# mega_nhakinh.net
KiCad netlist of a schematic drawn in Altium Designer
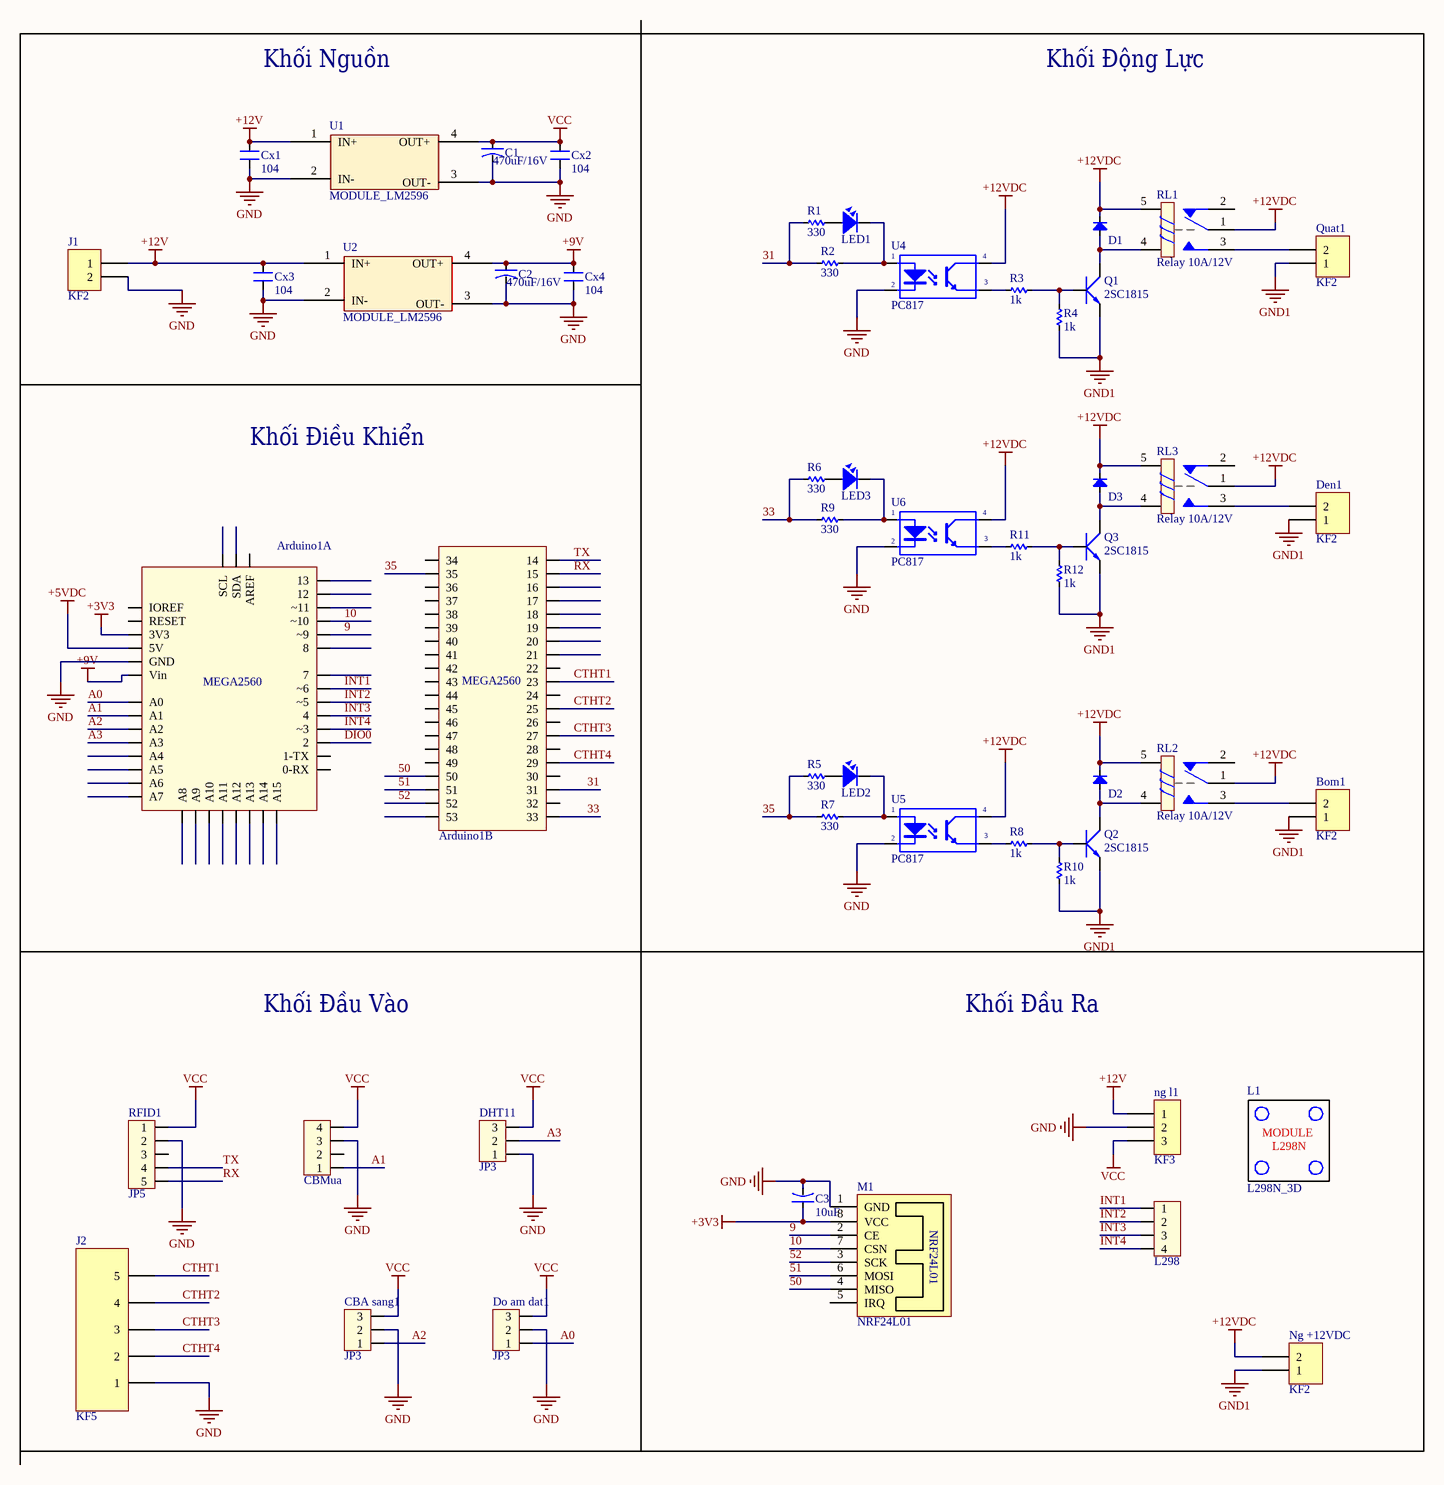
[diagram p0: mega nhakinh.SchDoc]

(export (version "E")
  (design (tool "Eeschema 10.0.6"))
  (components
    (comp (ref "Arduino1")
      (value "Arduino Mega2560")
      (footprint "Arduino MEGA2560")
      (description "Arduino MEGA2560")
      (libsource (lib "LIBRARY") (part "Arduino Mega2560"))
    )
    (comp (ref "Bom1")
      (value "KF2")
      (footprint "KF2-5.08")
      (fields
        (field (name "MANUFACTURER") "Würth Elektronik eiSos GmbH")
        (field (name "PARTNO") "691103110002")
        (field (name "CREATED BY") "Karrer Zheng")
      )
      (libsource (lib "LIBRARY") (part "KF2"))
    )
    (comp (ref "C1")
      (value "470uF/16V")
      (footprint "CA-ALU-10R")
      (description "Capacitor (Semiconductor SIM Model)")
      (fields (field (name "PUBLISHER") "Altium Limited"))
      (libsource (lib "LIBRARY") (part "CN-ALU-DIP"))
    )
    (comp (ref "C2")
      (value "470uF/16V")
      (footprint "CA-ALU-10R")
      (description "Capacitor (Semiconductor SIM Model)")
      (fields (field (name "PUBLISHER") "Altium Limited"))
      (libsource (lib "LIBRARY") (part "CN-ALU-DIP"))
    )
    (comp (ref "C3")
      (value "10uF")
      (footprint "CA-ALU-6.3R")
      (description "Capacitor (Semiconductor SIM Model)")
      (fields (field (name "PUBLISHER") "Altium Limited"))
      (libsource (lib "LIBRARY") (part "CN-ALU-DIP"))
    )
    (comp (ref "CBA sang1")
      (value "JP3")
      (footprint "CON3")
      (description "Connector 3")
      (libsource (lib "lib 1") (part "Con3"))
    )
    (comp (ref "Cx1") (value "104") (footprint "CN2-T") (libsource (lib "LIBRARY") (part "CN")))
    (comp (ref "Cx2") (value "104") (footprint "CN2-T") (libsource (lib "LIBRARY") (part "CN")))
    (comp (ref "Cx3") (value "104") (footprint "CN2-T") (libsource (lib "LIBRARY") (part "CN")))
    (comp (ref "Cx4") (value "104") (footprint "CN2-T") (libsource (lib "LIBRARY") (part "CN")))
    (comp (ref "D1")
      (value "Diode")
      (footprint "DIO-1A-SMALL")
      (description "Default Diode")
      (fields (field (name "PUBLISHER") "Altium Limited"))
      (libsource (lib "LIBRARY") (part "Diode"))
    )
    (comp (ref "D2")
      (value "Diode")
      (footprint "DIO-1A-SMALL")
      (description "Default Diode")
      (fields (field (name "PUBLISHER") "Altium Limited"))
      (libsource (lib "LIBRARY") (part "Diode"))
    )
    (comp (ref "D3")
      (value "Diode")
      (footprint "DIO-1A-SMALL")
      (description "Default Diode")
      (fields (field (name "PUBLISHER") "Altium Limited"))
      (libsource (lib "LIBRARY") (part "Diode"))
    )
    (comp (ref "Den1")
      (value "KF2")
      (footprint "KF2-5.08")
      (fields
        (field (name "MANUFACTURER") "Würth Elektronik eiSos GmbH")
        (field (name "PARTNO") "691103110002")
        (field (name "CREATED BY") "Karrer Zheng")
      )
      (libsource (lib "LIBRARY") (part "KF2"))
    )
    (comp (ref "DHT11")
      (value "JP3")
      (footprint "CON3")
      (description "Connector 3")
      (libsource (lib "lib 1") (part "Con3"))
    )
    (comp (ref "Do am dat1")
      (value "JP3")
      (footprint "CON3")
      (description "Connector 3")
      (libsource (lib "lib 1") (part "Con3"))
    )
    (comp (ref "J1")
      (value "KF2")
      (footprint "KF2-5.08")
      (fields
        (field (name "MANUFACTURER") "Würth Elektronik eiSos GmbH")
        (field (name "PARTNO") "691103110002")
        (field (name "CREATED BY") "Karrer Zheng")
      )
      (libsource (lib "") (part "KF2_1"))
    )
    (comp (ref "J2")
      (value "KF5")
      (footprint "KF5-5")
      (fields
        (field (name "MANUFACTURER") "Würth Elektronik eiSos GmbH")
        (field (name "PARTNO") "691133710005")
        (field (name "CREATED BY") "Baojun Chen")
      )
      (libsource (lib "LIBRARY") (part "KF5"))
    )
    (comp (ref "JP1")
      (value "L298")
      (footprint "CON4")
      (description "Connector 4")
      (libsource (lib "lib 1") (part "Con4"))
    )
    (comp (ref "JP2")
      (value "CBMua")
      (footprint "CON4")
      (description "Connector 4")
      (libsource (lib "") (part "Con4_1"))
    )
    (comp (ref "L1")
      (value "L298N_3D")
      (footprint "BaDinh_Library:L298N_3D")
      (libsource (lib "BaDinh_Library") (part "L298N_3D"))
    )
    (comp (ref "LED1")
      (value "LED")
      (footprint "LED-5MM-BLUE")
      (description "LED Single colour Green and Red")
      (libsource (lib "LIBRARY") (part "LED"))
    )
    (comp (ref "LED2")
      (value "LED")
      (footprint "LED-5MM-BLUE")
      (description "LED Single colour Green and Red")
      (libsource (lib "LIBRARY") (part "LED"))
    )
    (comp (ref "LED3")
      (value "LED")
      (footprint "LED-5MM-BLUE")
      (description "LED Single colour Green and Red")
      (libsource (lib "LIBRARY") (part "LED"))
    )
    (comp (ref "M1") (value "NRF24L01") (footprint "NRF24L01") (libsource (lib "LIBRARY") (part "NRF24L01")))
    (comp (ref "Ng +12VDC")
      (value "KF2")
      (footprint "KF2-5.08")
      (fields
        (field (name "MANUFACTURER") "Würth Elektronik eiSos GmbH")
        (field (name "PARTNO") "691103110002")
        (field (name "CREATED BY") "Karrer Zheng")
      )
      (libsource (lib "LIBRARY") (part "KF2"))
    )
    (comp (ref "ng l1")
      (value "KF3")
      (footprint "KF3-3.5")
      (fields
        (field (name "MANUFACTURER") "Würth Elektronik eiSos GmbH")
        (field (name "PARTNO") "691103110003")
        (field (name "CREATED BY") "Karrer Zheng")
      )
      (libsource (lib "LIBRARY") (part "KF3"))
    )
    (comp (ref "Q1")
      (value "2SC1815")
      (footprint "TO92-123")
      (description "NPN 600mW, ECB")
      (libsource (lib "LIBRARY") (part "2SC1815"))
    )
    (comp (ref "Q2")
      (value "2SC1815")
      (footprint "TO92-123")
      (description "NPN 600mW, ECB")
      (libsource (lib "LIBRARY") (part "2SC1815"))
    )
    (comp (ref "Q3")
      (value "2SC1815")
      (footprint "TO92-123")
      (description "NPN 600mW, ECB")
      (libsource (lib "LIBRARY") (part "2SC1815"))
    )
    (comp (ref "Quat1")
      (value "KF2")
      (footprint "KF2-5.08")
      (fields
        (field (name "MANUFACTURER") "Würth Elektronik eiSos GmbH")
        (field (name "PARTNO") "691103110002")
        (field (name "CREATED BY") "Karrer Zheng")
      )
      (libsource (lib "LIBRARY") (part "KF2"))
    )
    (comp (ref "R1")
      (value "330")
      (footprint "RES-1/4W-SMALL")
      (description "Res")
      (fields
        (field (name "MANUFACTURER") "Generic Components")
        (field (name "PUBLISHER") "Altium Hobart Technology Centre")
      )
      (libsource (lib "LIBRARY") (part "Res"))
    )
    (comp (ref "R2")
      (value "330")
      (footprint "RES-1/4W-SMALL")
      (description "Res")
      (fields
        (field (name "MANUFACTURER") "Generic Components")
        (field (name "PUBLISHER") "Altium Hobart Technology Centre")
      )
      (libsource (lib "LIBRARY") (part "Res"))
    )
    (comp (ref "R3")
      (value "1k")
      (footprint "RES-1/4W-SMALL")
      (description "Res")
      (fields
        (field (name "MANUFACTURER") "Generic Components")
        (field (name "PUBLISHER") "Altium Hobart Technology Centre")
      )
      (libsource (lib "LIBRARY") (part "Res"))
    )
    (comp (ref "R4")
      (value "1k")
      (footprint "RES-1/4W-SMALL")
      (description "Res")
      (fields
        (field (name "MANUFACTURER") "Generic Components")
        (field (name "PUBLISHER") "Altium Hobart Technology Centre")
      )
      (libsource (lib "LIBRARY") (part "Res"))
    )
    (comp (ref "R5")
      (value "330")
      (footprint "RES-1/4W-SMALL")
      (description "Res")
      (fields
        (field (name "MANUFACTURER") "Generic Components")
        (field (name "PUBLISHER") "Altium Hobart Technology Centre")
      )
      (libsource (lib "LIBRARY") (part "Res"))
    )
    (comp (ref "R6")
      (value "330")
      (footprint "RES-1/4W-SMALL")
      (description "Res")
      (fields
        (field (name "MANUFACTURER") "Generic Components")
        (field (name "PUBLISHER") "Altium Hobart Technology Centre")
      )
      (libsource (lib "LIBRARY") (part "Res"))
    )
    (comp (ref "R7")
      (value "330")
      (footprint "RES-1/4W-SMALL")
      (description "Res")
      (fields
        (field (name "MANUFACTURER") "Generic Components")
        (field (name "PUBLISHER") "Altium Hobart Technology Centre")
      )
      (libsource (lib "LIBRARY") (part "Res"))
    )
    (comp (ref "R8")
      (value "1k")
      (footprint "RES-1/4W-SMALL")
      (description "Res")
      (fields
        (field (name "MANUFACTURER") "Generic Components")
        (field (name "PUBLISHER") "Altium Hobart Technology Centre")
      )
      (libsource (lib "LIBRARY") (part "Res"))
    )
    (comp (ref "R9")
      (value "330")
      (footprint "RES-1/4W-SMALL")
      (description "Res")
      (fields
        (field (name "MANUFACTURER") "Generic Components")
        (field (name "PUBLISHER") "Altium Hobart Technology Centre")
      )
      (libsource (lib "LIBRARY") (part "Res"))
    )
    (comp (ref "R10")
      (value "1k")
      (footprint "RES-1/4W-SMALL")
      (description "Res")
      (fields
        (field (name "MANUFACTURER") "Generic Components")
        (field (name "PUBLISHER") "Altium Hobart Technology Centre")
      )
      (libsource (lib "LIBRARY") (part "Res"))
    )
    (comp (ref "R11")
      (value "1k")
      (footprint "RES-1/4W-SMALL")
      (description "Res")
      (fields
        (field (name "MANUFACTURER") "Generic Components")
        (field (name "PUBLISHER") "Altium Hobart Technology Centre")
      )
      (libsource (lib "LIBRARY") (part "Res"))
    )
    (comp (ref "R12")
      (value "1k")
      (footprint "RES-1/4W-SMALL")
      (description "Res")
      (fields
        (field (name "MANUFACTURER") "Generic Components")
        (field (name "PUBLISHER") "Altium Hobart Technology Centre")
      )
      (libsource (lib "LIBRARY") (part "Res"))
    )
    (comp (ref "RFID1")
      (value "JP5")
      (footprint "CON5")
      (description "Connector 5")
      (libsource (lib "lib 1") (part "Con5"))
    )
    (comp (ref "RL1")
      (value "Relay 10A/12V")
      (footprint "RELAY 5")
      (description "Relay SPDT,10A - 12VDC 5 Pin")
      (libsource (lib "LIBRARY") (part "Relay 5"))
    )
    (comp (ref "RL2")
      (value "Relay 10A/12V")
      (footprint "RELAY 5")
      (description "Relay SPDT,10A - 12VDC 5 Pin")
      (libsource (lib "LIBRARY") (part "Relay 5"))
    )
    (comp (ref "RL3")
      (value "Relay 10A/12V")
      (footprint "RELAY 5")
      (description "Relay SPDT,10A - 12VDC 5 Pin")
      (libsource (lib "LIBRARY") (part "Relay 5"))
    )
    (comp (ref "U1")
      (value "MODULE_LM2596")
      (footprint "BaDinh_Library:MODULE_LM2596")
      (libsource (lib "BaDinh_Library") (part "MODULE_LM2596"))
    )
    (comp (ref "U2")
      (value "MODULE_LM2596")
      (footprint "BaDinh_Library:MODULE_LM2596")
      (libsource (lib "BaDinh_Library") (part "MODULE_LM2596"))
    )
    (comp (ref "U4")
      (value "PC817")
      (footprint "DIP4")
      (description "Single Opto")
      (libsource (lib "LIBRARY") (part "PC817"))
    )
    (comp (ref "U5")
      (value "PC817")
      (footprint "DIP4")
      (description "Single Opto")
      (libsource (lib "LIBRARY") (part "PC817"))
    )
    (comp (ref "U6")
      (value "PC817")
      (footprint "DIP4")
      (description "Single Opto")
      (libsource (lib "LIBRARY") (part "PC817"))
    )
  )
  (nets
    (net (code "1") (name "+3V3") (class "Default")
      (node (ref "Arduino1") (pin "3V3") (pinfunction "3V3_3V3") (pintype "passive"))
      (node (ref "C3") (pin "1") (pinfunction "1_1") (pintype "passive"))
      (node (ref "M1") (pin "8") (pinfunction "VCC_8") (pintype "passive"))
    )
    (net (code "2") (name "+5VDC") (class "Default")
      (node (ref "Arduino1") (pin "5V") (pinfunction "5V_5V") (pintype "passive"))
    )
    (net (code "3") (name "+9V") (class "Default")
      (node (ref "Arduino1") (pin "Vin") (pinfunction "Vin_Vin") (pintype "passive"))
      (node (ref "C2") (pin "1") (pinfunction "1_1") (pintype "passive"))
      (node (ref "Cx4") (pin "2") (pinfunction "2_2") (pintype "passive"))
      (node (ref "U2") (pin "4") (pinfunction "OUT+_4") (pintype "passive"))
    )
    (net (code "4") (name "+12V") (class "Default")
      (node (ref "Cx1") (pin "2") (pinfunction "2_2") (pintype "passive"))
      (node (ref "Cx3") (pin "2") (pinfunction "2_2") (pintype "passive"))
      (node (ref "J1") (pin "1") (pinfunction "1_1") (pintype "passive"))
      (node (ref "U1") (pin "1") (pinfunction "IN+_1") (pintype "passive"))
      (node (ref "U2") (pin "1") (pinfunction "IN+_1") (pintype "passive"))
      (node (ref "ng l1") (pin "1") (pinfunction "1_1") (pintype "passive"))
    )
    (net (code "5") (name "+12VDC") (class "Default")
      (node (ref "D1") (pin "2") (pinfunction "K_2") (pintype "passive"))
      (node (ref "D2") (pin "2") (pinfunction "K_2") (pintype "passive"))
      (node (ref "D3") (pin "2") (pinfunction "K_2") (pintype "passive"))
      (node (ref "Ng +12VDC") (pin "2") (pinfunction "2_2") (pintype "passive"))
      (node (ref "RL1") (pin "1") (pinfunction "1_1") (pintype "passive"))
      (node (ref "RL1") (pin "5") (pinfunction "5_5") (pintype "passive"))
      (node (ref "RL2") (pin "1") (pinfunction "1_1") (pintype "passive"))
      (node (ref "RL2") (pin "5") (pinfunction "5_5") (pintype "passive"))
      (node (ref "RL3") (pin "1") (pinfunction "1_1") (pintype "passive"))
      (node (ref "RL3") (pin "5") (pinfunction "5_5") (pintype "passive"))
      (node (ref "U4") (pin "4") (pinfunction "C_4") (pintype "passive"))
      (node (ref "U5") (pin "4") (pinfunction "C_4") (pintype "passive"))
      (node (ref "U6") (pin "4") (pinfunction "C_4") (pintype "passive"))
    )
    (net (code "6") (name "/9") (class "Default")
      (node (ref "Arduino1") (pin "~9") (pinfunction "~9_~9") (pintype "passive"))
      (node (ref "M1") (pin "2") (pinfunction "CE_2") (pintype "passive"))
    )
    (net (code "7") (name "/10") (class "Default")
      (node (ref "Arduino1") (pin "~10") (pinfunction "~10_~10") (pintype "passive"))
      (node (ref "M1") (pin "7") (pinfunction "CSN_7") (pintype "passive"))
    )
    (net (code "8") (name "/31") (class "Default")
      (node (ref "Arduino1") (pin "31") (pinfunction "31_31") (pintype "passive"))
      (node (ref "R1") (pin "1") (pinfunction "1_1") (pintype "passive"))
      (node (ref "R2") (pin "1") (pinfunction "1_1") (pintype "passive"))
    )
    (net (code "9") (name "/33") (class "Default")
      (node (ref "Arduino1") (pin "33") (pinfunction "33_33") (pintype "passive"))
      (node (ref "R6") (pin "1") (pinfunction "1_1") (pintype "passive"))
      (node (ref "R9") (pin "1") (pinfunction "1_1") (pintype "passive"))
    )
    (net (code "10") (name "/35") (class "Default")
      (node (ref "Arduino1") (pin "35") (pinfunction "35_35") (pintype "passive"))
      (node (ref "R5") (pin "1") (pinfunction "1_1") (pintype "passive"))
      (node (ref "R7") (pin "1") (pinfunction "1_1") (pintype "passive"))
    )
    (net (code "11") (name "/50") (class "Default")
      (node (ref "Arduino1") (pin "50") (pinfunction "50_50") (pintype "passive"))
      (node (ref "M1") (pin "4") (pinfunction "MISO_4") (pintype "passive"))
    )
    (net (code "12") (name "/51") (class "Default")
      (node (ref "Arduino1") (pin "51") (pinfunction "51_51") (pintype "passive"))
      (node (ref "M1") (pin "6") (pinfunction "MOSI_6") (pintype "passive"))
    )
    (net (code "13") (name "/52") (class "Default")
      (node (ref "Arduino1") (pin "52") (pinfunction "52_52") (pintype "passive"))
      (node (ref "M1") (pin "3") (pinfunction "SCK_3") (pintype "passive"))
    )
    (net (code "14") (name "/A0") (class "Default")
      (node (ref "Arduino1") (pin "A0") (pinfunction "A0_A0") (pintype "passive"))
      (node (ref "Do am dat1") (pin "1") (pinfunction "1_1") (pintype "passive"))
    )
    (net (code "15") (name "/A1") (class "Default")
      (node (ref "Arduino1") (pin "A1") (pinfunction "A1_A1") (pintype "passive"))
      (node (ref "JP2") (pin "1") (pinfunction "1_1") (pintype "passive"))
    )
    (net (code "16") (name "/A2") (class "Default")
      (node (ref "Arduino1") (pin "A2") (pinfunction "A2_A2") (pintype "passive"))
      (node (ref "CBA sang1") (pin "1") (pinfunction "1_1") (pintype "passive"))
    )
    (net (code "17") (name "/A3") (class "Default")
      (node (ref "Arduino1") (pin "A3") (pinfunction "A3_A3") (pintype "passive"))
      (node (ref "DHT11") (pin "2") (pinfunction "2_2") (pintype "passive"))
    )
    (net (code "18") (name "/CTHT1") (class "Default")
      (node (ref "Arduino1") (pin "23") (pinfunction "23_23") (pintype "passive"))
      (node (ref "J2") (pin "5") (pinfunction "5_5") (pintype "passive"))
    )
    (net (code "19") (name "/CTHT2") (class "Default")
      (node (ref "Arduino1") (pin "25") (pinfunction "25_25") (pintype "passive"))
      (node (ref "J2") (pin "4") (pinfunction "4_4") (pintype "passive"))
    )
    (net (code "20") (name "/CTHT3") (class "Default")
      (node (ref "Arduino1") (pin "27") (pinfunction "27_27") (pintype "passive"))
      (node (ref "J2") (pin "3") (pinfunction "3_3") (pintype "passive"))
    )
    (net (code "21") (name "/CTHT4") (class "Default")
      (node (ref "Arduino1") (pin "29") (pinfunction "29_29") (pintype "passive"))
      (node (ref "J2") (pin "2") (pinfunction "2_2") (pintype "passive"))
    )
    (net (code "22") (name "/DIO0") (class "Default")
      (node (ref "Arduino1") (pin "2") (pinfunction "2_2") (pintype "passive"))
    )
    (net (code "23") (name "/INT1") (class "Default")
      (node (ref "Arduino1") (pin "~6") (pinfunction "~6_~6") (pintype "passive"))
      (node (ref "JP1") (pin "1") (pinfunction "1_1") (pintype "passive"))
    )
    (net (code "24") (name "/INT2") (class "Default")
      (node (ref "Arduino1") (pin "~5") (pinfunction "~5_~5") (pintype "passive"))
      (node (ref "JP1") (pin "2") (pinfunction "2_2") (pintype "passive"))
    )
    (net (code "25") (name "/INT3") (class "Default")
      (node (ref "Arduino1") (pin "4") (pinfunction "4_4") (pintype "passive"))
      (node (ref "JP1") (pin "3") (pinfunction "3_3") (pintype "passive"))
    )
    (net (code "26") (name "/INT4") (class "Default")
      (node (ref "Arduino1") (pin "~3") (pinfunction "~3_~3") (pintype "passive"))
      (node (ref "JP1") (pin "4") (pinfunction "4_4") (pintype "passive"))
    )
    (net (code "27") (name "/RX") (class "Default")
      (node (ref "Arduino1") (pin "15") (pinfunction "15_15") (pintype "passive"))
      (node (ref "RFID1") (pin "5") (pinfunction "5_5") (pintype "passive"))
    )
    (net (code "28") (name "/TX") (class "Default")
      (node (ref "Arduino1") (pin "14") (pinfunction "14_14") (pintype "passive"))
      (node (ref "RFID1") (pin "4") (pinfunction "4_4") (pintype "passive"))
    )
    (net (code "29") (name "GND") (class "Default")
      (node (ref "Arduino1") (pin "GND") (pinfunction "GND_GND") (pintype "passive"))
      (node (ref "C1") (pin "2") (pinfunction "2_2") (pintype "passive"))
      (node (ref "C2") (pin "2") (pinfunction "2_2") (pintype "passive"))
      (node (ref "C3") (pin "2") (pinfunction "2_2") (pintype "passive"))
      (node (ref "CBA sang1") (pin "2") (pinfunction "2_2") (pintype "passive"))
      (node (ref "Cx1") (pin "1") (pinfunction "1_1") (pintype "passive"))
      (node (ref "Cx2") (pin "1") (pinfunction "1_1") (pintype "passive"))
      (node (ref "Cx3") (pin "1") (pinfunction "1_1") (pintype "passive"))
      (node (ref "Cx4") (pin "1") (pinfunction "1_1") (pintype "passive"))
      (node (ref "DHT11") (pin "1") (pinfunction "1_1") (pintype "passive"))
      (node (ref "Do am dat1") (pin "2") (pinfunction "2_2") (pintype "passive"))
      (node (ref "J1") (pin "2") (pinfunction "2_2") (pintype "passive"))
      (node (ref "J2") (pin "1") (pinfunction "1_1") (pintype "passive"))
      (node (ref "JP2") (pin "3") (pinfunction "3_3") (pintype "passive"))
      (node (ref "M1") (pin "1") (pinfunction "GND_1") (pintype "passive"))
      (node (ref "RFID1") (pin "2") (pinfunction "2_2") (pintype "passive"))
      (node (ref "U1") (pin "2") (pinfunction "IN-_2") (pintype "passive"))
      (node (ref "U1") (pin "3") (pinfunction "OUT-_3") (pintype "passive"))
      (node (ref "U2") (pin "2") (pinfunction "IN-_2") (pintype "passive"))
      (node (ref "U2") (pin "3") (pinfunction "OUT-_3") (pintype "passive"))
      (node (ref "U4") (pin "2") (pinfunction "K_2") (pintype "passive"))
      (node (ref "U5") (pin "2") (pinfunction "K_2") (pintype "passive"))
      (node (ref "U6") (pin "2") (pinfunction "K_2") (pintype "passive"))
      (node (ref "ng l1") (pin "2") (pinfunction "2_2") (pintype "passive"))
    )
    (net (code "30") (name "GND1") (class "Default")
      (node (ref "Bom1") (pin "1") (pinfunction "1_1") (pintype "passive"))
      (node (ref "Den1") (pin "1") (pinfunction "1_1") (pintype "passive"))
      (node (ref "Ng +12VDC") (pin "1") (pinfunction "1_1") (pintype "passive"))
      (node (ref "Q1") (pin "1") (pinfunction "E_1") (pintype "passive"))
      (node (ref "Q2") (pin "1") (pinfunction "E_1") (pintype "passive"))
      (node (ref "Q3") (pin "1") (pinfunction "E_1") (pintype "passive"))
      (node (ref "Quat1") (pin "1") (pinfunction "1_1") (pintype "passive"))
      (node (ref "R10") (pin "2") (pinfunction "2_2") (pintype "passive"))
      (node (ref "R12") (pin "2") (pinfunction "2_2") (pintype "passive"))
      (node (ref "R4") (pin "2") (pinfunction "2_2") (pintype "passive"))
    )
    (net (code "31") (name "Net-(Bom1-Pad2)") (class "Default")
      (node (ref "Bom1") (pin "2") (pinfunction "2_2") (pintype "passive"))
      (node (ref "RL2") (pin "3") (pinfunction "3_3") (pintype "passive"))
    )
    (net (code "32") (name "Net-(D1-A)") (class "Default")
      (node (ref "D1") (pin "1") (pinfunction "A_1") (pintype "passive"))
      (node (ref "Q1") (pin "2") (pinfunction "C_2") (pintype "passive"))
      (node (ref "RL1") (pin "4") (pinfunction "4_4") (pintype "passive"))
    )
    (net (code "33") (name "Net-(D2-A)") (class "Default")
      (node (ref "D2") (pin "1") (pinfunction "A_1") (pintype "passive"))
      (node (ref "Q2") (pin "2") (pinfunction "C_2") (pintype "passive"))
      (node (ref "RL2") (pin "4") (pinfunction "4_4") (pintype "passive"))
    )
    (net (code "34") (name "Net-(D3-A)") (class "Default")
      (node (ref "D3") (pin "1") (pinfunction "A_1") (pintype "passive"))
      (node (ref "Q3") (pin "2") (pinfunction "C_2") (pintype "passive"))
      (node (ref "RL3") (pin "4") (pinfunction "4_4") (pintype "passive"))
    )
    (net (code "35") (name "Net-(Den1-Pad2)") (class "Default")
      (node (ref "Den1") (pin "2") (pinfunction "2_2") (pintype "passive"))
      (node (ref "RL3") (pin "3") (pinfunction "3_3") (pintype "passive"))
    )
    (net (code "36") (name "Net-(LED1-Pad1)") (class "Default")
      (node (ref "LED1") (pin "1") (pinfunction "1_1") (pintype "passive"))
      (node (ref "R1") (pin "2") (pinfunction "2_2") (pintype "passive"))
    )
    (net (code "37") (name "Net-(LED2-Pad1)") (class "Default")
      (node (ref "LED2") (pin "1") (pinfunction "1_1") (pintype "passive"))
      (node (ref "R5") (pin "2") (pinfunction "2_2") (pintype "passive"))
    )
    (net (code "38") (name "Net-(LED3-Pad1)") (class "Default")
      (node (ref "LED3") (pin "1") (pinfunction "1_1") (pintype "passive"))
      (node (ref "R6") (pin "2") (pinfunction "2_2") (pintype "passive"))
    )
    (net (code "39") (name "Net-(Q1-B)") (class "Default")
      (node (ref "Q1") (pin "3") (pinfunction "B_3") (pintype "passive"))
      (node (ref "R3") (pin "2") (pinfunction "2_2") (pintype "passive"))
      (node (ref "R4") (pin "1") (pinfunction "1_1") (pintype "passive"))
    )
    (net (code "40") (name "Net-(Q2-B)") (class "Default")
      (node (ref "Q2") (pin "3") (pinfunction "B_3") (pintype "passive"))
      (node (ref "R10") (pin "1") (pinfunction "1_1") (pintype "passive"))
      (node (ref "R8") (pin "2") (pinfunction "2_2") (pintype "passive"))
    )
    (net (code "41") (name "Net-(Q3-B)") (class "Default")
      (node (ref "Q3") (pin "3") (pinfunction "B_3") (pintype "passive"))
      (node (ref "R11") (pin "2") (pinfunction "2_2") (pintype "passive"))
      (node (ref "R12") (pin "1") (pinfunction "1_1") (pintype "passive"))
    )
    (net (code "42") (name "Net-(Quat1-Pad2)") (class "Default")
      (node (ref "Quat1") (pin "2") (pinfunction "2_2") (pintype "passive"))
      (node (ref "RL1") (pin "3") (pinfunction "3_3") (pintype "passive"))
    )
    (net (code "43") (name "Net-(U4-A)") (class "Default")
      (node (ref "LED1") (pin "2") (pinfunction "2_2") (pintype "passive"))
      (node (ref "R2") (pin "2") (pinfunction "2_2") (pintype "passive"))
      (node (ref "U4") (pin "1") (pinfunction "A_1") (pintype "passive"))
    )
    (net (code "44") (name "Net-(U4-E)") (class "Default")
      (node (ref "R3") (pin "1") (pinfunction "1_1") (pintype "passive"))
      (node (ref "U4") (pin "3") (pinfunction "E_3") (pintype "passive"))
    )
    (net (code "45") (name "Net-(U5-A)") (class "Default")
      (node (ref "LED2") (pin "2") (pinfunction "2_2") (pintype "passive"))
      (node (ref "R7") (pin "2") (pinfunction "2_2") (pintype "passive"))
      (node (ref "U5") (pin "1") (pinfunction "A_1") (pintype "passive"))
    )
    (net (code "46") (name "Net-(U5-E)") (class "Default")
      (node (ref "R8") (pin "1") (pinfunction "1_1") (pintype "passive"))
      (node (ref "U5") (pin "3") (pinfunction "E_3") (pintype "passive"))
    )
    (net (code "47") (name "Net-(U6-A)") (class "Default")
      (node (ref "LED3") (pin "2") (pinfunction "2_2") (pintype "passive"))
      (node (ref "R9") (pin "2") (pinfunction "2_2") (pintype "passive"))
      (node (ref "U6") (pin "1") (pinfunction "A_1") (pintype "passive"))
    )
    (net (code "48") (name "Net-(U6-E)") (class "Default")
      (node (ref "R11") (pin "1") (pinfunction "1_1") (pintype "passive"))
      (node (ref "U6") (pin "3") (pinfunction "E_3") (pintype "passive"))
    )
    (net (code "49") (name "VCC") (class "Default")
      (node (ref "C1") (pin "1") (pinfunction "1_1") (pintype "passive"))
      (node (ref "CBA sang1") (pin "3") (pinfunction "3_3") (pintype "passive"))
      (node (ref "Cx2") (pin "2") (pinfunction "2_2") (pintype "passive"))
      (node (ref "DHT11") (pin "3") (pinfunction "3_3") (pintype "passive"))
      (node (ref "Do am dat1") (pin "3") (pinfunction "3_3") (pintype "passive"))
      (node (ref "JP2") (pin "4") (pinfunction "4_4") (pintype "passive"))
      (node (ref "RFID1") (pin "1") (pinfunction "1_1") (pintype "passive"))
      (node (ref "U1") (pin "4") (pinfunction "OUT+_4") (pintype "passive"))
      (node (ref "ng l1") (pin "3") (pinfunction "3_3") (pintype "passive"))
    )
    (net (code "50") (name "unconnected-(Arduino1-Pad0-RX)") (class "Default")
      (node (ref "Arduino1") (pin "0-RX") (pinfunction "0-RX_0-RX") (pintype "passive"))
    )
    (net (code "51") (name "unconnected-(Arduino1-Pad1-TX)") (class "Default")
      (node (ref "Arduino1") (pin "1-TX") (pinfunction "1-TX_1-TX") (pintype "passive"))
    )
    (net (code "52") (name "unconnected-(Arduino1-Pad7)") (class "Default")
      (node (ref "Arduino1") (pin "7") (pinfunction "7_7") (pintype "passive"))
    )
    (net (code "53") (name "unconnected-(Arduino1-Pad8)") (class "Default")
      (node (ref "Arduino1") (pin "8") (pinfunction "8_8") (pintype "passive"))
    )
    (net (code "54") (name "unconnected-(Arduino1-Pad12)") (class "Default")
      (node (ref "Arduino1") (pin "12") (pinfunction "12_12") (pintype "passive"))
    )
    (net (code "55") (name "unconnected-(Arduino1-Pad13)") (class "Default")
      (node (ref "Arduino1") (pin "13") (pinfunction "13_13") (pintype "passive"))
    )
    (net (code "56") (name "unconnected-(Arduino1-Pad16)") (class "Default")
      (node (ref "Arduino1") (pin "16") (pinfunction "16_16") (pintype "passive"))
    )
    (net (code "57") (name "unconnected-(Arduino1-Pad17)") (class "Default")
      (node (ref "Arduino1") (pin "17") (pinfunction "17_17") (pintype "passive"))
    )
    (net (code "58") (name "unconnected-(Arduino1-Pad18)") (class "Default")
      (node (ref "Arduino1") (pin "18") (pinfunction "18_18") (pintype "passive"))
    )
    (net (code "59") (name "unconnected-(Arduino1-Pad19)") (class "Default")
      (node (ref "Arduino1") (pin "19") (pinfunction "19_19") (pintype "passive"))
    )
    (net (code "60") (name "unconnected-(Arduino1-Pad20)") (class "Default")
      (node (ref "Arduino1") (pin "20") (pinfunction "20_20") (pintype "passive"))
    )
    (net (code "61") (name "unconnected-(Arduino1-Pad21)") (class "Default")
      (node (ref "Arduino1") (pin "21") (pinfunction "21_21") (pintype "passive"))
    )
    (net (code "62") (name "unconnected-(Arduino1-Pad22)") (class "Default")
      (node (ref "Arduino1") (pin "22") (pinfunction "22_22") (pintype "passive"))
    )
    (net (code "63") (name "unconnected-(Arduino1-Pad24)") (class "Default")
      (node (ref "Arduino1") (pin "24") (pinfunction "24_24") (pintype "passive"))
    )
    (net (code "64") (name "unconnected-(Arduino1-Pad26)") (class "Default")
      (node (ref "Arduino1") (pin "26") (pinfunction "26_26") (pintype "passive"))
    )
    (net (code "65") (name "unconnected-(Arduino1-Pad28)") (class "Default")
      (node (ref "Arduino1") (pin "28") (pinfunction "28_28") (pintype "passive"))
    )
    (net (code "66") (name "unconnected-(Arduino1-Pad30)") (class "Default")
      (node (ref "Arduino1") (pin "30") (pinfunction "30_30") (pintype "passive"))
    )
    (net (code "67") (name "unconnected-(Arduino1-Pad32)") (class "Default")
      (node (ref "Arduino1") (pin "32") (pinfunction "32_32") (pintype "passive"))
    )
    (net (code "68") (name "unconnected-(Arduino1-Pad34)") (class "Default")
      (node (ref "Arduino1") (pin "34") (pinfunction "34_34") (pintype "passive"))
    )
    (net (code "69") (name "unconnected-(Arduino1-Pad36)") (class "Default")
      (node (ref "Arduino1") (pin "36") (pinfunction "36_36") (pintype "passive"))
    )
    (net (code "70") (name "unconnected-(Arduino1-Pad37)") (class "Default")
      (node (ref "Arduino1") (pin "37") (pinfunction "37_37") (pintype "passive"))
    )
    (net (code "71") (name "unconnected-(Arduino1-Pad38)") (class "Default")
      (node (ref "Arduino1") (pin "38") (pinfunction "38_38") (pintype "passive"))
    )
    (net (code "72") (name "unconnected-(Arduino1-Pad39)") (class "Default")
      (node (ref "Arduino1") (pin "39") (pinfunction "39_39") (pintype "passive"))
    )
    (net (code "73") (name "unconnected-(Arduino1-Pad40)") (class "Default")
      (node (ref "Arduino1") (pin "40") (pinfunction "40_40") (pintype "passive"))
    )
    (net (code "74") (name "unconnected-(Arduino1-Pad41)") (class "Default")
      (node (ref "Arduino1") (pin "41") (pinfunction "41_41") (pintype "passive"))
    )
    (net (code "75") (name "unconnected-(Arduino1-Pad42)") (class "Default")
      (node (ref "Arduino1") (pin "42") (pinfunction "42_42") (pintype "passive"))
    )
    (net (code "76") (name "unconnected-(Arduino1-Pad43)") (class "Default")
      (node (ref "Arduino1") (pin "43") (pinfunction "43_43") (pintype "passive"))
    )
    (net (code "77") (name "unconnected-(Arduino1-Pad44)") (class "Default")
      (node (ref "Arduino1") (pin "44") (pinfunction "44_44") (pintype "passive"))
    )
    (net (code "78") (name "unconnected-(Arduino1-Pad45)") (class "Default")
      (node (ref "Arduino1") (pin "45") (pinfunction "45_45") (pintype "passive"))
    )
    (net (code "79") (name "unconnected-(Arduino1-Pad46)") (class "Default")
      (node (ref "Arduino1") (pin "46") (pinfunction "46_46") (pintype "passive"))
    )
    (net (code "80") (name "unconnected-(Arduino1-Pad47)") (class "Default")
      (node (ref "Arduino1") (pin "47") (pinfunction "47_47") (pintype "passive"))
    )
    (net (code "81") (name "unconnected-(Arduino1-Pad48)") (class "Default")
      (node (ref "Arduino1") (pin "48") (pinfunction "48_48") (pintype "passive"))
    )
    (net (code "82") (name "unconnected-(Arduino1-Pad49)") (class "Default")
      (node (ref "Arduino1") (pin "49") (pinfunction "49_49") (pintype "passive"))
    )
    (net (code "83") (name "unconnected-(Arduino1-Pad53)") (class "Default")
      (node (ref "Arduino1") (pin "53") (pinfunction "53_53") (pintype "passive"))
    )
    (net (code "84") (name "unconnected-(Arduino1-PadA4)") (class "Default")
      (node (ref "Arduino1") (pin "A4") (pinfunction "A4_A4") (pintype "passive"))
    )
    (net (code "85") (name "unconnected-(Arduino1-PadA5)") (class "Default")
      (node (ref "Arduino1") (pin "A5") (pinfunction "A5_A5") (pintype "passive"))
    )
    (net (code "86") (name "unconnected-(Arduino1-PadA6)") (class "Default")
      (node (ref "Arduino1") (pin "A6") (pinfunction "A6_A6") (pintype "passive"))
    )
    (net (code "87") (name "unconnected-(Arduino1-PadA7)") (class "Default")
      (node (ref "Arduino1") (pin "A7") (pinfunction "A7_A7") (pintype "passive"))
    )
    (net (code "88") (name "unconnected-(Arduino1-PadA8)") (class "Default")
      (node (ref "Arduino1") (pin "A8") (pinfunction "A8_A8") (pintype "passive"))
    )
    (net (code "89") (name "unconnected-(Arduino1-PadA9)") (class "Default")
      (node (ref "Arduino1") (pin "A9") (pinfunction "A9_A9") (pintype "passive"))
    )
    (net (code "90") (name "unconnected-(Arduino1-PadA10)") (class "Default")
      (node (ref "Arduino1") (pin "A10") (pinfunction "A10_A10") (pintype "passive"))
    )
    (net (code "91") (name "unconnected-(Arduino1-PadA11)") (class "Default")
      (node (ref "Arduino1") (pin "A11") (pinfunction "A11_A11") (pintype "passive"))
    )
    (net (code "92") (name "unconnected-(Arduino1-PadA12)") (class "Default")
      (node (ref "Arduino1") (pin "A12") (pinfunction "A12_A12") (pintype "passive"))
    )
    (net (code "93") (name "unconnected-(Arduino1-PadA13)") (class "Default")
      (node (ref "Arduino1") (pin "A13") (pinfunction "A13_A13") (pintype "passive"))
    )
    (net (code "94") (name "unconnected-(Arduino1-PadA14)") (class "Default")
      (node (ref "Arduino1") (pin "A14") (pinfunction "A14_A14") (pintype "passive"))
    )
    (net (code "95") (name "unconnected-(Arduino1-PadA15)") (class "Default")
      (node (ref "Arduino1") (pin "A15") (pinfunction "A15_A15") (pintype "passive"))
    )
    (net (code "96") (name "unconnected-(Arduino1-PadAREF)") (class "Default")
      (node (ref "Arduino1") (pin "AREF") (pinfunction "AREF_AREF") (pintype "passive"))
    )
    (net (code "97") (name "unconnected-(Arduino1-PadIOREF)") (class "Default")
      (node (ref "Arduino1") (pin "IOREF") (pinfunction "IOREF_IOREF") (pintype "passive"))
    )
    (net (code "98") (name "unconnected-(Arduino1-PadRESET)") (class "Default")
      (node (ref "Arduino1") (pin "RESET") (pinfunction "RESET_RESET") (pintype "passive"))
    )
    (net (code "99") (name "unconnected-(Arduino1-PadSCL)") (class "Default")
      (node (ref "Arduino1") (pin "SCL") (pinfunction "SCL_SCL") (pintype "passive"))
    )
    (net (code "100") (name "unconnected-(Arduino1-PadSDA)") (class "Default")
      (node (ref "Arduino1") (pin "SDA") (pinfunction "SDA_SDA") (pintype "passive"))
    )
    (net (code "101") (name "unconnected-(Arduino1-Pad~11)") (class "Default")
      (node (ref "Arduino1") (pin "~11") (pinfunction "~11_~11") (pintype "passive"))
    )
    (net (code "102") (name "unconnected-(JP2-Pad2)") (class "Default")
      (node (ref "JP2") (pin "2") (pinfunction "2_2") (pintype "passive"))
    )
    (net (code "103") (name "unconnected-(M1-IRQ-Pad5)") (class "Default")
      (node (ref "M1") (pin "5") (pinfunction "IRQ_5") (pintype "passive"))
    )
    (net (code "104") (name "unconnected-(RFID1-Pad3)") (class "Default")
      (node (ref "RFID1") (pin "3") (pinfunction "3_3") (pintype "passive"))
    )
    (net (code "105") (name "unconnected-(RL1-Pad2)") (class "Default")
      (node (ref "RL1") (pin "2") (pinfunction "2_2") (pintype "passive"))
    )
    (net (code "106") (name "unconnected-(RL2-Pad2)") (class "Default")
      (node (ref "RL2") (pin "2") (pinfunction "2_2") (pintype "passive"))
    )
    (net (code "107") (name "unconnected-(RL3-Pad2)") (class "Default")
      (node (ref "RL3") (pin "2") (pinfunction "2_2") (pintype "passive"))
    )
  )
)
